# CamBienMau.net
KiCad netlist of a schematic drawn in Altium Designer
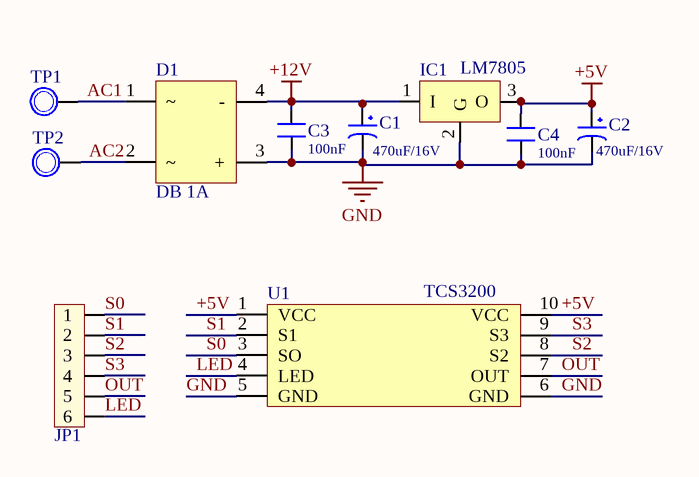
[diagram p0: CamBienMau.SchDoc]

(export (version "E")
  (design (tool "Eeschema 10.0.6"))
  (components
    (comp (ref "C1")
      (value "470uF/16V")
      (footprint "C-TANT-7343")
      (libsource (lib "MrQuan") (part "Capacitor"))
    )
    (comp (ref "C2")
      (value "470uF/16V")
      (footprint "C-TANT-7343")
      (libsource (lib "MrQuan") (part "Capacitor"))
    )
    (comp (ref "C3") (value "100nF") (footprint "CER-0805") (libsource (lib "MrQuan") (part "Ceramic")))
    (comp (ref "C4") (value "100nF") (footprint "CER-0805") (libsource (lib "MrQuan") (part "Ceramic")))
    (comp (ref "D1")
      (value "DB 1A")
      (footprint "D-DB-1A-SMD")
      (libsource (lib "doAnTotNghiep2017Lib") (part "DB"))
    )
    (comp (ref "IC1")
      (value "LM7805")
      (footprint "TO252-123")
      (description "Positive Voltage Regulator")
      (fields (field (name "PUBLISHER") "Altium Limited"))
      (libsource (lib "LIBRARY") (part "LM78xx"))
    )
    (comp (ref "JP1") (value "JP6 PIN") (footprint "JP6") (libsource (lib "syhaunguyen") (part "JP6")))
    (comp (ref "TP1") (value "TP") (footprint "TP") (libsource (lib "MrQuan") (part "TP")))
    (comp (ref "TP2") (value "TP") (footprint "TP") (libsource (lib "MrQuan") (part "TP")))
    (comp (ref "U1") (value "TCS3200") (libsource (lib "MrQuan") (part "TCS3200")))
  )
  (nets
    (net (code "1") (name "+5V") (class "Default")
      (node (ref "C2") (pin "1") (pinfunction "1_1") (pintype "passive"))
      (node (ref "C4") (pin "2") (pinfunction "2_2") (pintype "passive"))
      (node (ref "IC1") (pin "3") (pinfunction "O_3") (pintype "power_in"))
      (node (ref "U1") (pin "1") (pinfunction "VCC_1") (pintype "passive"))
      (node (ref "U1") (pin "10") (pinfunction "VCC_10") (pintype "passive"))
    )
    (net (code "2") (name "+12V") (class "Default")
      (node (ref "C1") (pin "1") (pinfunction "1_1") (pintype "passive"))
      (node (ref "C3") (pin "2") (pinfunction "2_2") (pintype "passive"))
      (node (ref "D1") (pin "4") (pinfunction "-_4") (pintype "passive"))
      (node (ref "IC1") (pin "1") (pinfunction "I_1") (pintype "power_in"))
    )
    (net (code "3") (name "/AC1") (class "Default")
      (node (ref "D1") (pin "1") (pinfunction "~_1") (pintype "passive"))
      (node (ref "TP1") (pin "1") (pintype "passive"))
    )
    (net (code "4") (name "/AC2") (class "Default")
      (node (ref "D1") (pin "2") (pinfunction "~_2") (pintype "passive"))
      (node (ref "TP2") (pin "1") (pintype "passive"))
    )
    (net (code "5") (name "/LED") (class "Default")
      (node (ref "JP1") (pin "6") (pinfunction "6_6") (pintype "passive"))
      (node (ref "U1") (pin "4") (pinfunction "LED_4") (pintype "passive"))
    )
    (net (code "6") (name "/OUT") (class "Default")
      (node (ref "JP1") (pin "5") (pinfunction "5_5") (pintype "passive"))
      (node (ref "U1") (pin "7") (pinfunction "OUT_7") (pintype "passive"))
    )
    (net (code "7") (name "/S0") (class "Default")
      (node (ref "JP1") (pin "1") (pinfunction "1_1") (pintype "passive"))
      (node (ref "U1") (pin "3") (pinfunction "SO_3") (pintype "passive"))
    )
    (net (code "8") (name "/S1") (class "Default")
      (node (ref "JP1") (pin "2") (pinfunction "2_2") (pintype "passive"))
      (node (ref "U1") (pin "2") (pinfunction "S1_2") (pintype "passive"))
    )
    (net (code "9") (name "/S2") (class "Default")
      (node (ref "JP1") (pin "3") (pinfunction "3_3") (pintype "passive"))
      (node (ref "U1") (pin "8") (pinfunction "S2_8") (pintype "passive"))
    )
    (net (code "10") (name "/S3") (class "Default")
      (node (ref "JP1") (pin "4") (pinfunction "4_4") (pintype "passive"))
      (node (ref "U1") (pin "9") (pinfunction "S3_9") (pintype "passive"))
    )
    (net (code "11") (name "GND") (class "Default")
      (node (ref "C1") (pin "2") (pinfunction "2_2") (pintype "passive"))
      (node (ref "C2") (pin "2") (pinfunction "2_2") (pintype "passive"))
      (node (ref "C3") (pin "1") (pinfunction "1_1") (pintype "passive"))
      (node (ref "C4") (pin "1") (pinfunction "1_1") (pintype "passive"))
      (node (ref "D1") (pin "3") (pinfunction "+_3") (pintype "passive"))
      (node (ref "IC1") (pin "2") (pinfunction "G_2") (pintype "power_in"))
      (node (ref "U1") (pin "5") (pinfunction "GND_5") (pintype "passive"))
      (node (ref "U1") (pin "6") (pinfunction "GND_6") (pintype "passive"))
    )
  )
)
